# DistributedVisionSchematicPage3.net
KiCad netlist of a schematic drawn in EAGLE
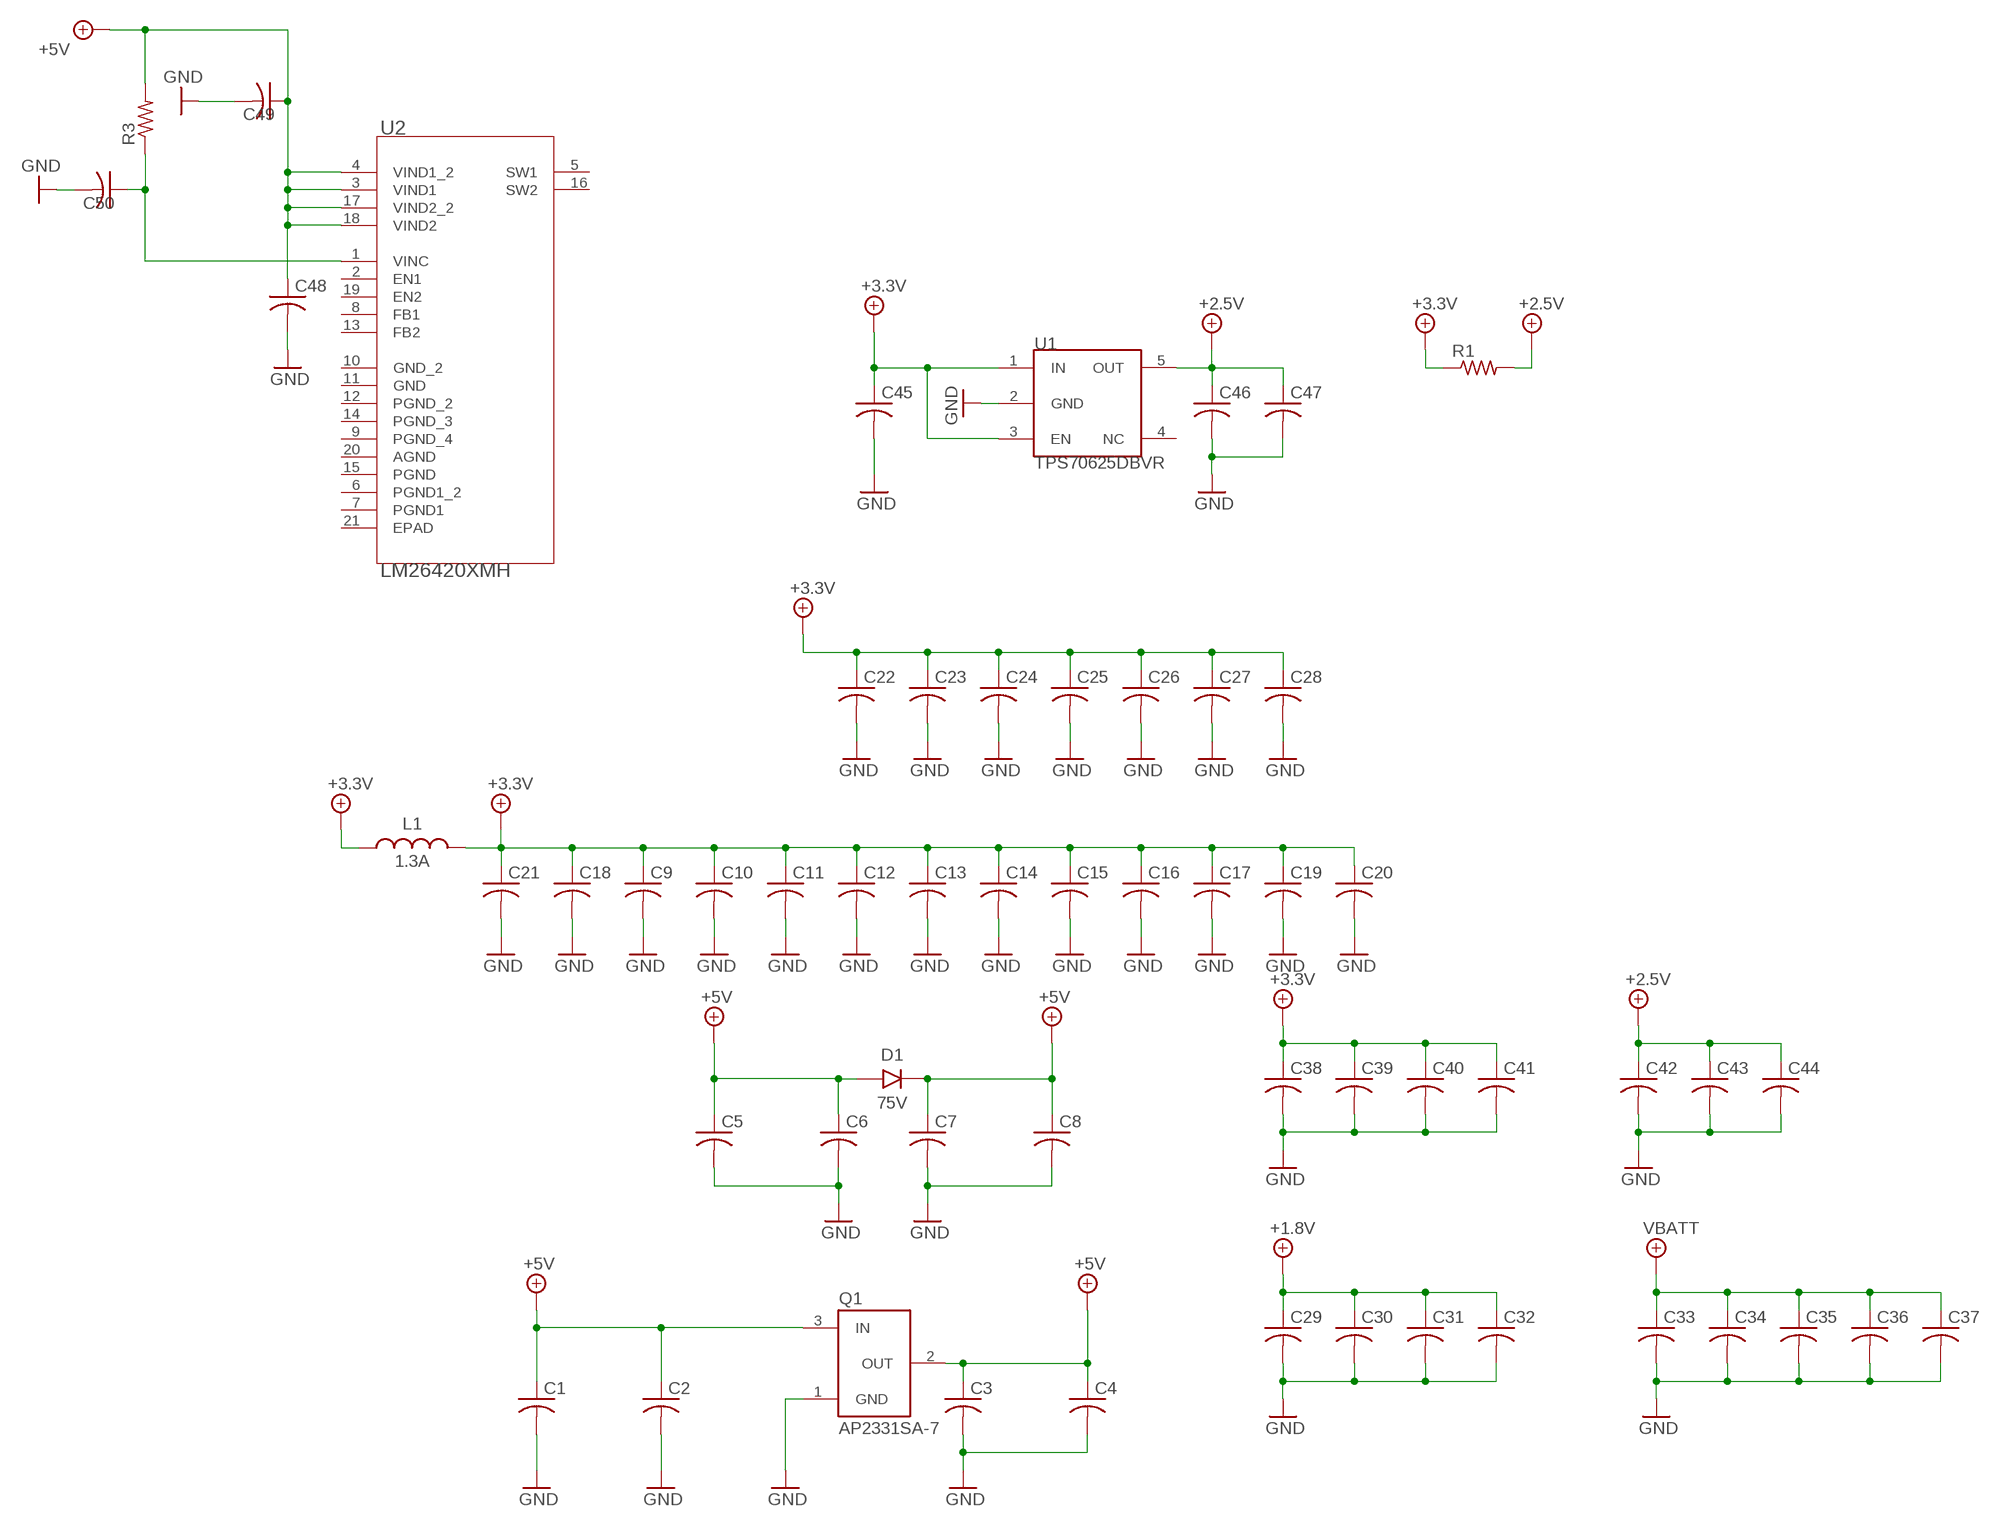
[diagram p0: schematic, sheet 2]

(export (version "E")
  (design (tool "Eeschema 10.0.6"))
  (components
    (comp (ref "C1")
      (value "C-USC0603")
      (footprint "eagle-import:C0603")
      (libsource (lib "eagle-import") (part "C-USC0603"))
    )
    (comp (ref "C2")
      (value "C-USC0603")
      (footprint "eagle-import:C0603")
      (libsource (lib "eagle-import") (part "C-USC0603"))
    )
    (comp (ref "C3")
      (value "C-USC0603")
      (footprint "eagle-import:C0603")
      (libsource (lib "eagle-import") (part "C-USC0603"))
    )
    (comp (ref "C4")
      (value "C-USC0603")
      (footprint "eagle-import:C0603")
      (libsource (lib "eagle-import") (part "C-USC0603"))
    )
    (comp (ref "C5")
      (value "C-USC0603")
      (footprint "eagle-import:C0603")
      (libsource (lib "eagle-import") (part "C-USC0603"))
    )
    (comp (ref "C6")
      (value "C-USC0603")
      (footprint "eagle-import:C0603")
      (libsource (lib "eagle-import") (part "C-USC0603"))
    )
    (comp (ref "C7")
      (value "C-USC0603")
      (footprint "eagle-import:C0603")
      (libsource (lib "eagle-import") (part "C-USC0603"))
    )
    (comp (ref "C8")
      (value "C-USC0603")
      (footprint "eagle-import:C0603")
      (libsource (lib "eagle-import") (part "C-USC0603"))
    )
    (comp (ref "C9")
      (value "C-USC0603")
      (footprint "eagle-import:C0603")
      (libsource (lib "eagle-import") (part "C-USC0603"))
    )
    (comp (ref "C10")
      (value "C-USC0603")
      (footprint "eagle-import:C0603")
      (libsource (lib "eagle-import") (part "C-USC0603"))
    )
    (comp (ref "C11")
      (value "C-USC0603")
      (footprint "eagle-import:C0603")
      (libsource (lib "eagle-import") (part "C-USC0603"))
    )
    (comp (ref "C12")
      (value "C-USC0603")
      (footprint "eagle-import:C0603")
      (libsource (lib "eagle-import") (part "C-USC0603"))
    )
    (comp (ref "C13")
      (value "C-USC0603")
      (footprint "eagle-import:C0603")
      (libsource (lib "eagle-import") (part "C-USC0603"))
    )
    (comp (ref "C14")
      (value "C-USC0603")
      (footprint "eagle-import:C0603")
      (libsource (lib "eagle-import") (part "C-USC0603"))
    )
    (comp (ref "C15")
      (value "C-USC0603")
      (footprint "eagle-import:C0603")
      (libsource (lib "eagle-import") (part "C-USC0603"))
    )
    (comp (ref "C16")
      (value "C-USC0603")
      (footprint "eagle-import:C0603")
      (libsource (lib "eagle-import") (part "C-USC0603"))
    )
    (comp (ref "C17")
      (value "C-USC0603")
      (footprint "eagle-import:C0603")
      (libsource (lib "eagle-import") (part "C-USC0603"))
    )
    (comp (ref "C18")
      (value "C-USC0603")
      (footprint "eagle-import:C0603")
      (libsource (lib "eagle-import") (part "C-USC0603"))
    )
    (comp (ref "C19")
      (value "C-USC0603")
      (footprint "eagle-import:C0603")
      (libsource (lib "eagle-import") (part "C-USC0603"))
    )
    (comp (ref "C20")
      (value "C-USC0603")
      (footprint "eagle-import:C0603")
      (libsource (lib "eagle-import") (part "C-USC0603"))
    )
    (comp (ref "C21")
      (value "C-USC0603")
      (footprint "eagle-import:C0603")
      (libsource (lib "eagle-import") (part "C-USC0603"))
    )
    (comp (ref "C22")
      (value "C-USC0603")
      (footprint "eagle-import:C0603")
      (libsource (lib "eagle-import") (part "C-USC0603"))
    )
    (comp (ref "C23")
      (value "C-USC0603")
      (footprint "eagle-import:C0603")
      (libsource (lib "eagle-import") (part "C-USC0603"))
    )
    (comp (ref "C24")
      (value "C-USC0603")
      (footprint "eagle-import:C0603")
      (libsource (lib "eagle-import") (part "C-USC0603"))
    )
    (comp (ref "C25")
      (value "C-USC0603")
      (footprint "eagle-import:C0603")
      (libsource (lib "eagle-import") (part "C-USC0603"))
    )
    (comp (ref "C26")
      (value "C-USC0603")
      (footprint "eagle-import:C0603")
      (libsource (lib "eagle-import") (part "C-USC0603"))
    )
    (comp (ref "C27")
      (value "C-USC0603")
      (footprint "eagle-import:C0603")
      (libsource (lib "eagle-import") (part "C-USC0603"))
    )
    (comp (ref "C28")
      (value "C-USC0603")
      (footprint "eagle-import:C0603")
      (libsource (lib "eagle-import") (part "C-USC0603"))
    )
    (comp (ref "C29")
      (value "C-USC0603")
      (footprint "eagle-import:C0603")
      (libsource (lib "eagle-import") (part "C-USC0603"))
    )
    (comp (ref "C30")
      (value "C-USC0603")
      (footprint "eagle-import:C0603")
      (libsource (lib "eagle-import") (part "C-USC0603"))
    )
    (comp (ref "C31")
      (value "C-USC0603")
      (footprint "eagle-import:C0603")
      (libsource (lib "eagle-import") (part "C-USC0603"))
    )
    (comp (ref "C32")
      (value "C-USC0603")
      (footprint "eagle-import:C0603")
      (libsource (lib "eagle-import") (part "C-USC0603"))
    )
    (comp (ref "C33")
      (value "C-USC0603")
      (footprint "eagle-import:C0603")
      (libsource (lib "eagle-import") (part "C-USC0603"))
    )
    (comp (ref "C34")
      (value "C-USC0603")
      (footprint "eagle-import:C0603")
      (libsource (lib "eagle-import") (part "C-USC0603"))
    )
    (comp (ref "C35")
      (value "C-USC0603")
      (footprint "eagle-import:C0603")
      (libsource (lib "eagle-import") (part "C-USC0603"))
    )
    (comp (ref "C36")
      (value "C-USC0603")
      (footprint "eagle-import:C0603")
      (libsource (lib "eagle-import") (part "C-USC0603"))
    )
    (comp (ref "C37")
      (value "C-USC0603")
      (footprint "eagle-import:C0603")
      (libsource (lib "eagle-import") (part "C-USC0603"))
    )
    (comp (ref "C38")
      (value "C-USC0603")
      (footprint "eagle-import:C0603")
      (libsource (lib "eagle-import") (part "C-USC0603"))
    )
    (comp (ref "C39")
      (value "C-USC0603")
      (footprint "eagle-import:C0603")
      (libsource (lib "eagle-import") (part "C-USC0603"))
    )
    (comp (ref "C40")
      (value "C-USC0603")
      (footprint "eagle-import:C0603")
      (libsource (lib "eagle-import") (part "C-USC0603"))
    )
    (comp (ref "C41")
      (value "C-USC0603")
      (footprint "eagle-import:C0603")
      (libsource (lib "eagle-import") (part "C-USC0603"))
    )
    (comp (ref "C42")
      (value "C-USC0603")
      (footprint "eagle-import:C0603")
      (libsource (lib "eagle-import") (part "C-USC0603"))
    )
    (comp (ref "C43")
      (value "C-USC0603")
      (footprint "eagle-import:C0603")
      (libsource (lib "eagle-import") (part "C-USC0603"))
    )
    (comp (ref "C44")
      (value "C-USC0603")
      (footprint "eagle-import:C0603")
      (libsource (lib "eagle-import") (part "C-USC0603"))
    )
    (comp (ref "C45")
      (value "C-USC0603")
      (footprint "eagle-import:C0603")
      (libsource (lib "eagle-import") (part "C-USC0603"))
    )
    (comp (ref "C46")
      (value "C-USC0603")
      (footprint "eagle-import:C0603")
      (libsource (lib "eagle-import") (part "C-USC0603"))
    )
    (comp (ref "C47")
      (value "C-USC0603")
      (footprint "eagle-import:C0603")
      (libsource (lib "eagle-import") (part "C-USC0603"))
    )
    (comp (ref "C48")
      (value "C-USC0603")
      (footprint "eagle-import:C0603")
      (libsource (lib "eagle-import") (part "C-USC0603"))
    )
    (comp (ref "C49")
      (value "C-USC0603")
      (footprint "eagle-import:C0603")
      (libsource (lib "eagle-import") (part "C-USC0603"))
    )
    (comp (ref "C50")
      (value "C-USC0603")
      (footprint "eagle-import:C0603")
      (libsource (lib "eagle-import") (part "C-USC0603"))
    )
    (comp (ref "D1")
      (value "75V")
      (footprint "eagle-import:SOD-323")
      (libsource (lib "eagle-import") (part "1N4148WX"))
    )
    (comp (ref "L1")
      (value "1.3A")
      (footprint "eagle-import:0805")
      (libsource (lib "eagle-import") (part "INDUCTOR_0805"))
    )
    (comp (ref "Q1")
      (value "AP2331SA-7")
      (footprint "eagle-import:SOT23")
      (libsource (lib "eagle-import") (part "AP2331SA-7"))
    )
    (comp (ref "R1")
      (value "R-US_R0603")
      (footprint "eagle-import:R0603")
      (libsource (lib "eagle-import") (part "R-US_R0603"))
    )
    (comp (ref "R3")
      (value "R-US_R0603")
      (footprint "eagle-import:R0603")
      (libsource (lib "eagle-import") (part "R-US_R0603"))
    )
    (comp (ref "U1")
      (value "TPS70625DBVR")
      (footprint "eagle-import:DBV0005A")
      (libsource (lib "eagle-import") (part "TPS70625DBVR"))
    )
    (comp (ref "U2")
      (value "LM26420XMH")
      (footprint "eagle-import:PWP0020A")
      (libsource (lib "eagle-import") (part "LM26420XMH"))
    )
  )
  (nets
    (net (code "1") (name "+1.8V") (class "Default")
      (node (ref "C29") (pin "1") (pinfunction "1_1") (pintype "passive"))
      (node (ref "C30") (pin "1") (pinfunction "1_1") (pintype "passive"))
      (node (ref "C31") (pin "1") (pinfunction "1_1") (pintype "passive"))
      (node (ref "C32") (pin "1") (pinfunction "1_1") (pintype "passive"))
    )
    (net (code "2") (name "+2.5V") (class "Default")
      (node (ref "C42") (pin "1") (pinfunction "1_1") (pintype "passive"))
      (node (ref "C43") (pin "1") (pinfunction "1_1") (pintype "passive"))
      (node (ref "C44") (pin "1") (pinfunction "1_1") (pintype "passive"))
      (node (ref "C46") (pin "1") (pinfunction "1_1") (pintype "passive"))
      (node (ref "C47") (pin "1") (pinfunction "1_1") (pintype "passive"))
      (node (ref "R1") (pin "2") (pinfunction "2_2") (pintype "passive"))
      (node (ref "U1") (pin "5") (pinfunction "OUT_5") (pintype "output"))
    )
    (net (code "3") (name "+3.3V") (class "Default")
      (node (ref "C10") (pin "1") (pinfunction "1_1") (pintype "passive"))
      (node (ref "C11") (pin "1") (pinfunction "1_1") (pintype "passive"))
      (node (ref "C12") (pin "1") (pinfunction "1_1") (pintype "passive"))
      (node (ref "C13") (pin "1") (pinfunction "1_1") (pintype "passive"))
      (node (ref "C14") (pin "1") (pinfunction "1_1") (pintype "passive"))
      (node (ref "C15") (pin "1") (pinfunction "1_1") (pintype "passive"))
      (node (ref "C16") (pin "1") (pinfunction "1_1") (pintype "passive"))
      (node (ref "C17") (pin "1") (pinfunction "1_1") (pintype "passive"))
      (node (ref "C18") (pin "1") (pinfunction "1_1") (pintype "passive"))
      (node (ref "C19") (pin "1") (pinfunction "1_1") (pintype "passive"))
      (node (ref "C20") (pin "1") (pinfunction "1_1") (pintype "passive"))
      (node (ref "C21") (pin "1") (pinfunction "1_1") (pintype "passive"))
      (node (ref "C22") (pin "1") (pinfunction "1_1") (pintype "passive"))
      (node (ref "C23") (pin "1") (pinfunction "1_1") (pintype "passive"))
      (node (ref "C24") (pin "1") (pinfunction "1_1") (pintype "passive"))
      (node (ref "C25") (pin "1") (pinfunction "1_1") (pintype "passive"))
      (node (ref "C26") (pin "1") (pinfunction "1_1") (pintype "passive"))
      (node (ref "C27") (pin "1") (pinfunction "1_1") (pintype "passive"))
      (node (ref "C28") (pin "1") (pinfunction "1_1") (pintype "passive"))
      (node (ref "C38") (pin "1") (pinfunction "1_1") (pintype "passive"))
      (node (ref "C39") (pin "1") (pinfunction "1_1") (pintype "passive"))
      (node (ref "C40") (pin "1") (pinfunction "1_1") (pintype "passive"))
      (node (ref "C41") (pin "1") (pinfunction "1_1") (pintype "passive"))
      (node (ref "C45") (pin "1") (pinfunction "1_1") (pintype "passive"))
      (node (ref "C9") (pin "1") (pinfunction "1_1") (pintype "passive"))
      (node (ref "L1") (pin "1") (pinfunction "1_1") (pintype "passive"))
      (node (ref "L1") (pin "2") (pinfunction "2_2") (pintype "passive"))
      (node (ref "R1") (pin "1") (pinfunction "1_1") (pintype "passive"))
      (node (ref "U1") (pin "1") (pinfunction "IN_1") (pintype "input"))
      (node (ref "U1") (pin "3") (pinfunction "EN_3") (pintype "bidirectional"))
    )
    (net (code "4") (name "+5V") (class "Default")
      (node (ref "C1") (pin "1") (pinfunction "1_1") (pintype "passive"))
      (node (ref "C2") (pin "1") (pinfunction "1_1") (pintype "passive"))
      (node (ref "C3") (pin "1") (pinfunction "1_1") (pintype "passive"))
      (node (ref "C4") (pin "1") (pinfunction "1_1") (pintype "passive"))
      (node (ref "C48") (pin "1") (pinfunction "1_1") (pintype "passive"))
      (node (ref "C49") (pin "1") (pinfunction "1_1") (pintype "passive"))
      (node (ref "C5") (pin "1") (pinfunction "1_1") (pintype "passive"))
      (node (ref "C6") (pin "1") (pinfunction "1_1") (pintype "passive"))
      (node (ref "C7") (pin "1") (pinfunction "1_1") (pintype "passive"))
      (node (ref "C8") (pin "1") (pinfunction "1_1") (pintype "passive"))
      (node (ref "D1") (pin "A") (pinfunction "A_A") (pintype "passive"))
      (node (ref "D1") (pin "C") (pinfunction "C_C") (pintype "passive"))
      (node (ref "Q1") (pin "2") (pinfunction "OUT_2") (pintype "bidirectional"))
      (node (ref "Q1") (pin "3") (pinfunction "IN_3") (pintype "bidirectional"))
      (node (ref "R3") (pin "2") (pinfunction "2_2") (pintype "passive"))
      (node (ref "U2") (pin "17") (pinfunction "VIND2_2_17") (pintype "power_in"))
      (node (ref "U2") (pin "18") (pinfunction "VIND2_18") (pintype "power_in"))
      (node (ref "U2") (pin "3") (pinfunction "VIND1_3") (pintype "power_in"))
      (node (ref "U2") (pin "4") (pinfunction "VIND1_2_4") (pintype "power_in"))
    )
    (net (code "5") (name "GND") (class "Default")
      (node (ref "C1") (pin "2") (pinfunction "2_2") (pintype "passive"))
      (node (ref "C10") (pin "2") (pinfunction "2_2") (pintype "passive"))
      (node (ref "C11") (pin "2") (pinfunction "2_2") (pintype "passive"))
      (node (ref "C12") (pin "2") (pinfunction "2_2") (pintype "passive"))
      (node (ref "C13") (pin "2") (pinfunction "2_2") (pintype "passive"))
      (node (ref "C14") (pin "2") (pinfunction "2_2") (pintype "passive"))
      (node (ref "C15") (pin "2") (pinfunction "2_2") (pintype "passive"))
      (node (ref "C16") (pin "2") (pinfunction "2_2") (pintype "passive"))
      (node (ref "C17") (pin "2") (pinfunction "2_2") (pintype "passive"))
      (node (ref "C18") (pin "2") (pinfunction "2_2") (pintype "passive"))
      (node (ref "C19") (pin "2") (pinfunction "2_2") (pintype "passive"))
      (node (ref "C2") (pin "2") (pinfunction "2_2") (pintype "passive"))
      (node (ref "C20") (pin "2") (pinfunction "2_2") (pintype "passive"))
      (node (ref "C21") (pin "2") (pinfunction "2_2") (pintype "passive"))
      (node (ref "C22") (pin "2") (pinfunction "2_2") (pintype "passive"))
      (node (ref "C23") (pin "2") (pinfunction "2_2") (pintype "passive"))
      (node (ref "C24") (pin "2") (pinfunction "2_2") (pintype "passive"))
      (node (ref "C25") (pin "2") (pinfunction "2_2") (pintype "passive"))
      (node (ref "C26") (pin "2") (pinfunction "2_2") (pintype "passive"))
      (node (ref "C27") (pin "2") (pinfunction "2_2") (pintype "passive"))
      (node (ref "C28") (pin "2") (pinfunction "2_2") (pintype "passive"))
      (node (ref "C29") (pin "2") (pinfunction "2_2") (pintype "passive"))
      (node (ref "C3") (pin "2") (pinfunction "2_2") (pintype "passive"))
      (node (ref "C30") (pin "2") (pinfunction "2_2") (pintype "passive"))
      (node (ref "C31") (pin "2") (pinfunction "2_2") (pintype "passive"))
      (node (ref "C32") (pin "2") (pinfunction "2_2") (pintype "passive"))
      (node (ref "C33") (pin "2") (pinfunction "2_2") (pintype "passive"))
      (node (ref "C34") (pin "2") (pinfunction "2_2") (pintype "passive"))
      (node (ref "C35") (pin "2") (pinfunction "2_2") (pintype "passive"))
      (node (ref "C36") (pin "2") (pinfunction "2_2") (pintype "passive"))
      (node (ref "C37") (pin "2") (pinfunction "2_2") (pintype "passive"))
      (node (ref "C38") (pin "2") (pinfunction "2_2") (pintype "passive"))
      (node (ref "C39") (pin "2") (pinfunction "2_2") (pintype "passive"))
      (node (ref "C4") (pin "2") (pinfunction "2_2") (pintype "passive"))
      (node (ref "C40") (pin "2") (pinfunction "2_2") (pintype "passive"))
      (node (ref "C41") (pin "2") (pinfunction "2_2") (pintype "passive"))
      (node (ref "C42") (pin "2") (pinfunction "2_2") (pintype "passive"))
      (node (ref "C43") (pin "2") (pinfunction "2_2") (pintype "passive"))
      (node (ref "C44") (pin "2") (pinfunction "2_2") (pintype "passive"))
      (node (ref "C45") (pin "2") (pinfunction "2_2") (pintype "passive"))
      (node (ref "C46") (pin "2") (pinfunction "2_2") (pintype "passive"))
      (node (ref "C47") (pin "2") (pinfunction "2_2") (pintype "passive"))
      (node (ref "C48") (pin "2") (pinfunction "2_2") (pintype "passive"))
      (node (ref "C49") (pin "2") (pinfunction "2_2") (pintype "passive"))
      (node (ref "C5") (pin "2") (pinfunction "2_2") (pintype "passive"))
      (node (ref "C50") (pin "2") (pinfunction "2_2") (pintype "passive"))
      (node (ref "C6") (pin "2") (pinfunction "2_2") (pintype "passive"))
      (node (ref "C7") (pin "2") (pinfunction "2_2") (pintype "passive"))
      (node (ref "C8") (pin "2") (pinfunction "2_2") (pintype "passive"))
      (node (ref "C9") (pin "2") (pinfunction "2_2") (pintype "passive"))
      (node (ref "Q1") (pin "1") (pinfunction "GND_1") (pintype "bidirectional"))
      (node (ref "U1") (pin "2") (pinfunction "GND_2") (pintype "power_in"))
    )
    (net (code "6") (name "Net-(U2-VINC)") (class "Default")
      (node (ref "C50") (pin "1") (pinfunction "1_1") (pintype "passive"))
      (node (ref "R3") (pin "1") (pinfunction "1_1") (pintype "passive"))
      (node (ref "U2") (pin "1") (pinfunction "VINC_1") (pintype "power_in"))
    )
    (net (code "7") (name "VBATT") (class "Default")
      (node (ref "C33") (pin "1") (pinfunction "1_1") (pintype "passive"))
      (node (ref "C34") (pin "1") (pinfunction "1_1") (pintype "passive"))
      (node (ref "C35") (pin "1") (pinfunction "1_1") (pintype "passive"))
      (node (ref "C36") (pin "1") (pinfunction "1_1") (pintype "passive"))
      (node (ref "C37") (pin "1") (pinfunction "1_1") (pintype "passive"))
    )
    (net (code "8") (name "unconnected-(U1-NC-Pad4)") (class "Default")
      (node (ref "U1") (pin "4") (pinfunction "NC_4") (pintype "no_connect"))
    )
    (net (code "9") (name "unconnected-(U2-AGND-Pad20)") (class "Default")
      (node (ref "U2") (pin "20") (pinfunction "AGND_20") (pintype "passive"))
    )
    (net (code "10") (name "unconnected-(U2-EN1-Pad2)") (class "Default")
      (node (ref "U2") (pin "2") (pinfunction "EN1_2") (pintype "input"))
    )
    (net (code "11") (name "unconnected-(U2-EN2-Pad19)") (class "Default")
      (node (ref "U2") (pin "19") (pinfunction "EN2_19") (pintype "input"))
    )
    (net (code "12") (name "unconnected-(U2-EPAD-Pad21)") (class "Default")
      (node (ref "U2") (pin "21") (pinfunction "EPAD_21") (pintype "passive"))
    )
    (net (code "13") (name "unconnected-(U2-FB1-Pad8)") (class "Default")
      (node (ref "U2") (pin "8") (pinfunction "FB1_8") (pintype "input"))
    )
    (net (code "14") (name "unconnected-(U2-FB2-Pad13)") (class "Default")
      (node (ref "U2") (pin "13") (pinfunction "FB2_13") (pintype "input"))
    )
    (net (code "15") (name "unconnected-(U2-GND-Pad11)") (class "Default")
      (node (ref "U2") (pin "11") (pinfunction "GND_11") (pintype "passive"))
    )
    (net (code "16") (name "unconnected-(U2-GND_2-Pad10)") (class "Default")
      (node (ref "U2") (pin "10") (pinfunction "GND_2_10") (pintype "passive"))
    )
    (net (code "17") (name "unconnected-(U2-PGND-Pad15)") (class "Default")
      (node (ref "U2") (pin "15") (pinfunction "PGND_15") (pintype "passive"))
    )
    (net (code "18") (name "unconnected-(U2-PGND1-Pad7)") (class "Default")
      (node (ref "U2") (pin "7") (pinfunction "PGND1_7") (pintype "passive"))
    )
    (net (code "19") (name "unconnected-(U2-PGND1_2-Pad6)") (class "Default")
      (node (ref "U2") (pin "6") (pinfunction "PGND1_2_6") (pintype "passive"))
    )
    (net (code "20") (name "unconnected-(U2-PGND_2-Pad12)") (class "Default")
      (node (ref "U2") (pin "12") (pinfunction "PGND_2_12") (pintype "passive"))
    )
    (net (code "21") (name "unconnected-(U2-PGND_3-Pad14)") (class "Default")
      (node (ref "U2") (pin "14") (pinfunction "PGND_3_14") (pintype "passive"))
    )
    (net (code "22") (name "unconnected-(U2-PGND_4-Pad9)") (class "Default")
      (node (ref "U2") (pin "9") (pinfunction "PGND_4_9") (pintype "passive"))
    )
    (net (code "23") (name "unconnected-(U2-SW1-Pad5)") (class "Default")
      (node (ref "U2") (pin "5") (pinfunction "SW1_5") (pintype "output"))
    )
    (net (code "24") (name "unconnected-(U2-SW2-Pad16)") (class "Default")
      (node (ref "U2") (pin "16") (pinfunction "SW2_16") (pintype "output"))
    )
  )
)
